# MCU042A_HOST_INTERFACE.net
KiCad netlist of a schematic drawn in Altium Designer
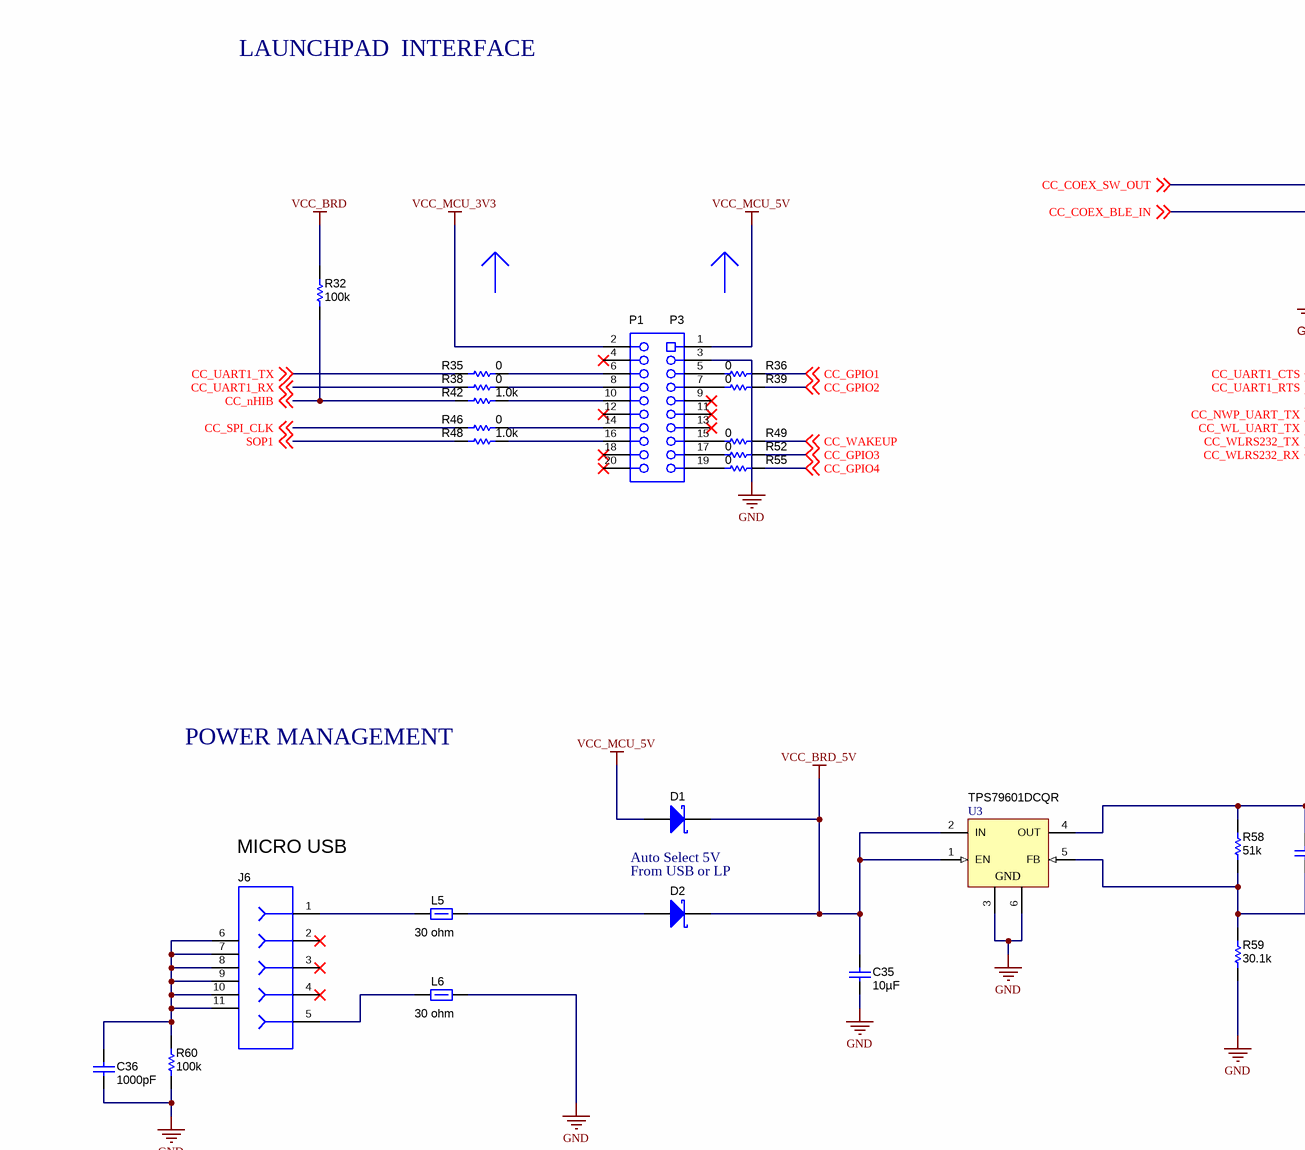
[diagram p0: MCU042A_HOST INTERFACE.SchDoc, top left]
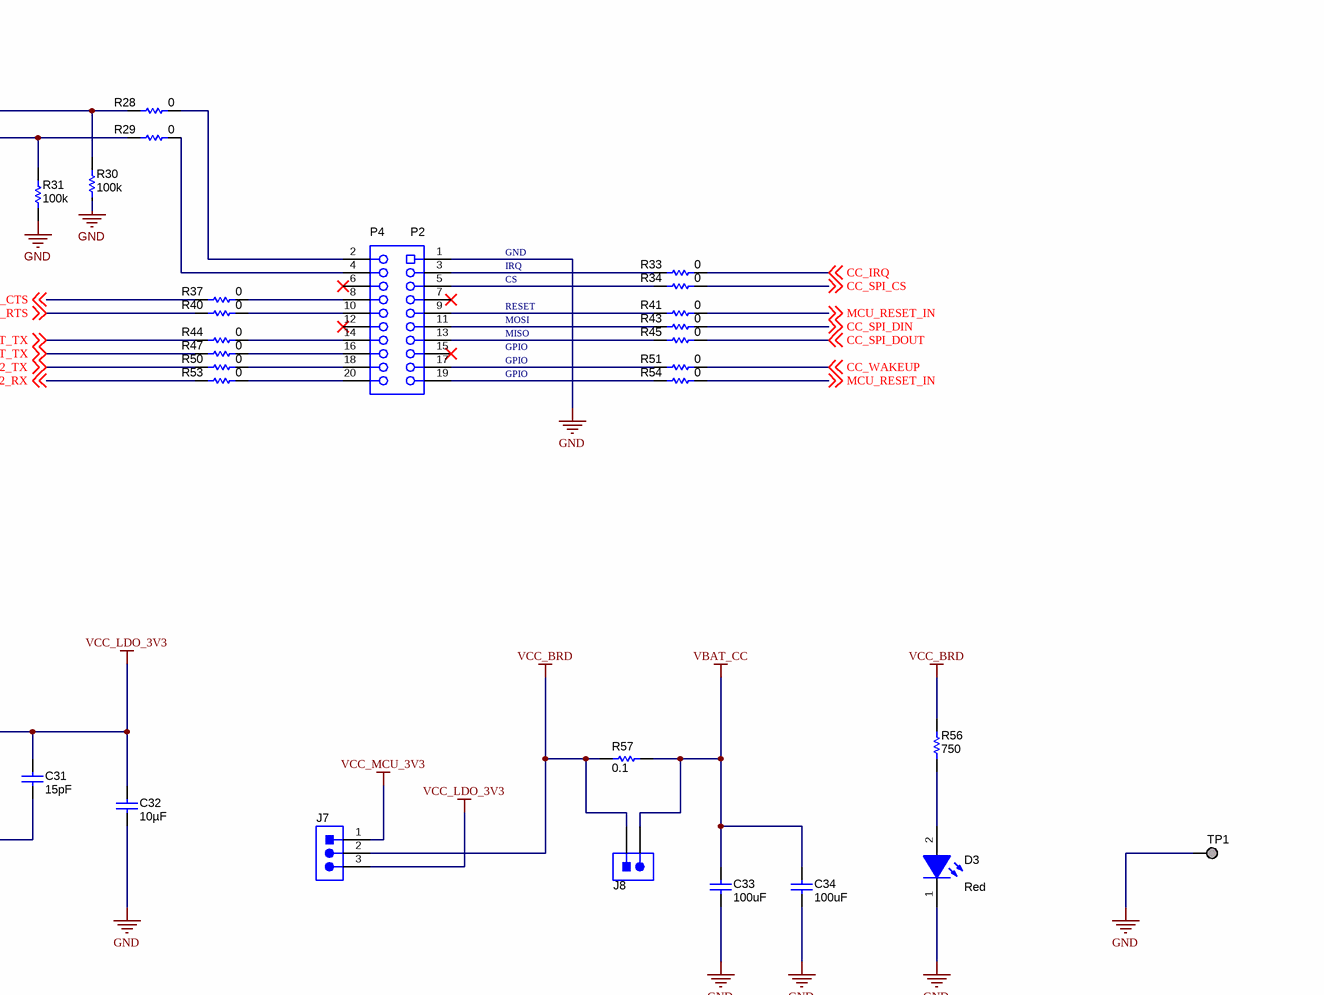
[diagram p1: MCU042A_HOST INTERFACE.SchDoc, top right]
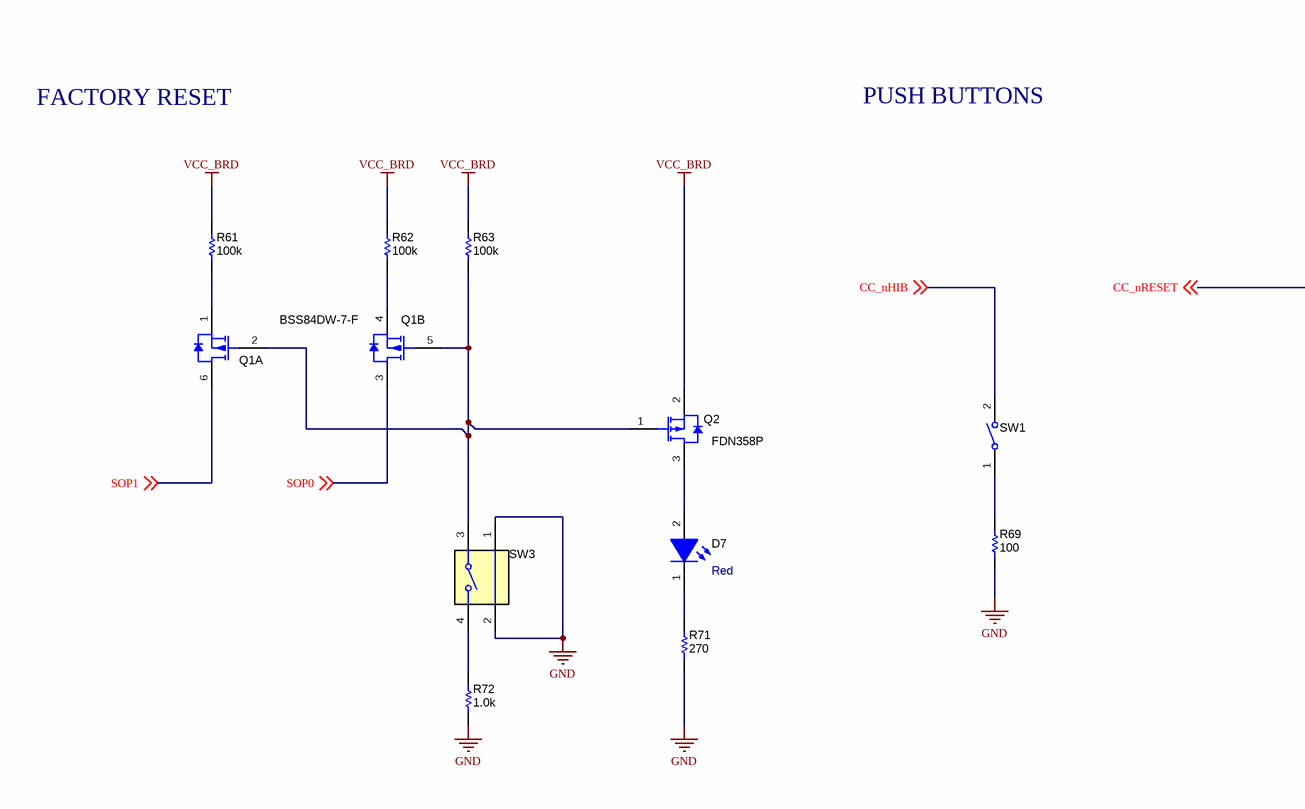
[diagram p2: MCU042A_HOST INTERFACE.SchDoc, bottom left]
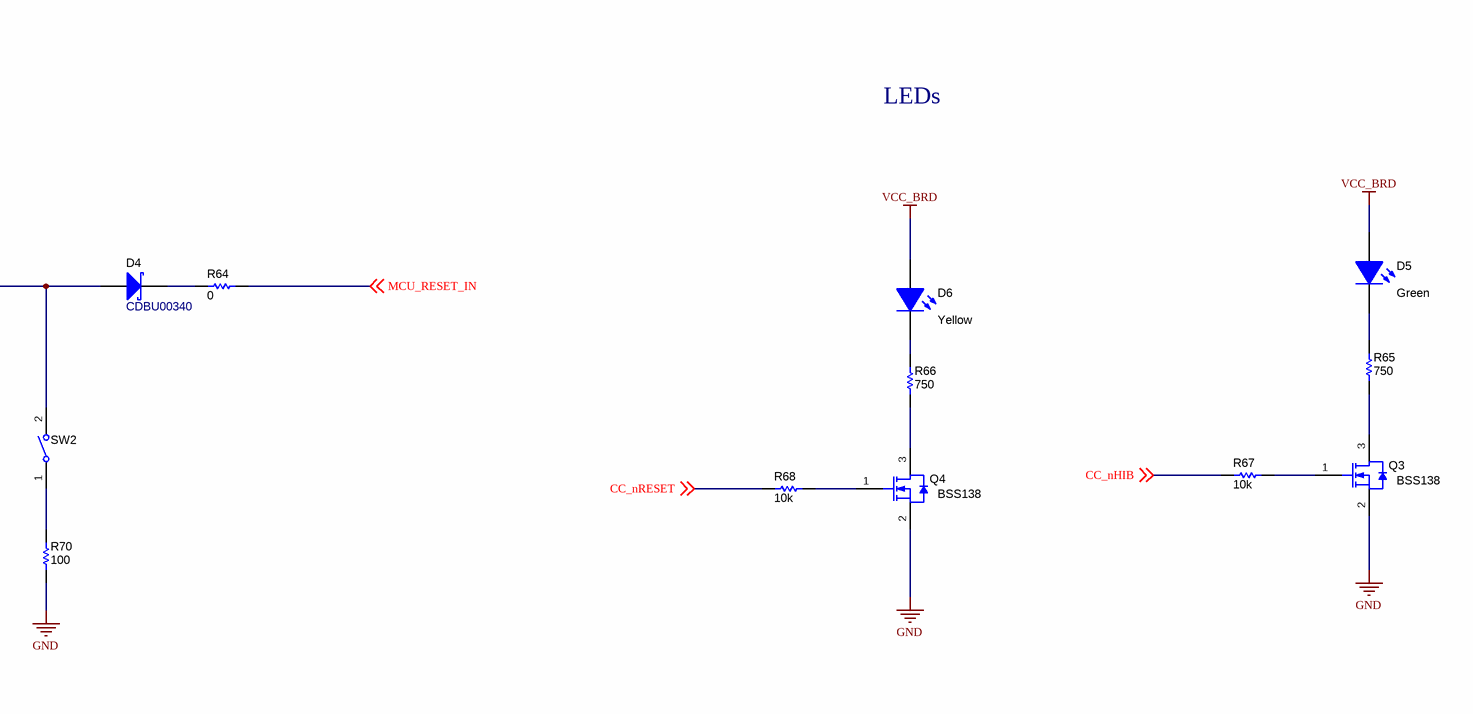
[diagram p3: MCU042A_HOST INTERFACE.SchDoc, bottom right]

(export (version "E")
  (design (tool "Eeschema 10.0.6"))
  (components
    (comp (ref "C31")
      (value "CMP-0006420-2")
      (footprint "0402")
      (description "CAP, CERM, 15 pF, 50 V, +/- 5%, C0G/NP0, 0402")
      (fields
        (field (name "PARTNUMBER") "CL05C150JB5NNNC")
        (field (name "VALUEDISPLAYED") "15pF")
        (field (name "MANUFACTURER") "SAMSUNG")
        (field (name "PUBLISHER") "Texas Instruments")
      )
      (libsource (lib "Altium Vault - TI") (part "CMP-0006420-2"))
    )
    (comp (ref "C32")
      (value "CL21A106KPFNNNE")
      (footprint "0805_HV")
      (description "CAP, CERM, 10 µF, 10 V,+/- 10%, X5R, 0805")
      (fields
        (field (name "VALUEDISPLAYED") "10µF")
        (field (name "MANUFACTURER") "Samsung Electro-Mechanics")
        (field (name "ALTERNATE PARTNUMBER") "GRM21BR61A106KE19L")
      )
      (libsource (lib "Altium Vault - TI") (part "Capacitor"))
    )
    (comp (ref "C33")
      (value "CMP-0008934-2")
      (footprint "1206_180")
      (description "CAP, CERM, 100 uF, 6.3 V, +/- 20%, X5R, 1206")
      (fields
        (field (name "PARTNUMBER") "GRM31CR60J107ME39L")
        (field (name "VALUEDISPLAYED") "100uF")
        (field (name "MANUFACTURER") "MuRata")
        (field (name "PUBLISHER") "Texas Instruments")
      )
      (libsource (lib "Altium Vault - TI") (part "CMP-0008934-2"))
    )
    (comp (ref "C34")
      (value "CMP-0008934-2")
      (footprint "1206_180")
      (description "CAP, CERM, 100 uF, 6.3 V, +/- 20%, X5R, 1206")
      (fields
        (field (name "PARTNUMBER") "GRM31CR60J107ME39L")
        (field (name "VALUEDISPLAYED") "100uF")
        (field (name "MANUFACTURER") "MuRata")
        (field (name "PUBLISHER") "Texas Instruments")
      )
      (libsource (lib "Altium Vault - TI") (part "CMP-0008934-2"))
    )
    (comp (ref "C35")
      (value "CL21A106KPFNNNE")
      (footprint "0805_HV")
      (description "CAP, CERM, 10 µF, 10 V,+/- 10%, X5R, 0805")
      (fields
        (field (name "VALUEDISPLAYED") "10µF")
        (field (name "MANUFACTURER") "Samsung Electro-Mechanics")
        (field (name "ALTERNATE PARTNUMBER") "GRM21BR61A106KE19L")
      )
      (libsource (lib "Altium Vault - TI") (part "Capacitor"))
    )
    (comp (ref "C36")
      (value "CL10B102KB8NNNC")
      (footprint "0603")
      (description "CAP, CERM, 1000 pF, 50 V,+/- 10%, X7R, 0603")
      (fields
        (field (name "VALUEDISPLAYED") "1000pF")
        (field (name "MANUFACTURER") "Samsung Electro-Mechanics")
        (field (name "ALTERNATE PARTNUMBER") "GRM188R61H102KA01D")
      )
      (libsource (lib "Altium Vault - TI") (part "Capacitor"))
    )
    (comp (ref "D1")
      (value "CMP-0028547-1")
      (footprint "SOD-123")
      (description "Diode, Schottky, 30 V, 1 A, SOD-123")
      (fields
        (field (name "PARTNUMBER") "MBR130T1G")
        (field (name "MANUFACTURER") "ON Semiconductor")
        (field (name "PUBLISHER") "Texas Instruments")
      )
      (libsource (lib "Altium Vault - TI") (part "CMP-0028547-1"))
    )
    (comp (ref "D2")
      (value "CMP-0028547-1")
      (footprint "SOD-123")
      (description "Diode, Schottky, 30 V, 1 A, SOD-123")
      (fields
        (field (name "PARTNUMBER") "MBR130T1G")
        (field (name "MANUFACTURER") "ON Semiconductor")
        (field (name "PUBLISHER") "Texas Instruments")
      )
      (libsource (lib "Altium Vault - TI") (part "CMP-0028547-1"))
    )
    (comp (ref "D3")
      (value "Red")
      (footprint "SML-31_Red")
      (description "LED, Red, SMD")
      (fields
        (field (name "MANUFACTURER") "Everlight")
        (field (name "PARTNUMBER") "19-217/R6C-AL1M2VY/3T")
        (field (name "PUBLISHER") "Texas Instruments")
      )
      (libsource (lib "Altium Vault - TI") (part "CMP-0002871-1"))
    )
    (comp (ref "D4")
      (value "CDBU00340")
      (footprint "SOD-523F")
      (description "Diode, Schottky, 45 V, 0.03 A, SOD-523F")
      (fields
        (field (name "MANUFACTURER") "Comchip Technology")
        (field (name "ALTERNATE PARTNUMBER") "CD0603-B00340")
      )
      (libsource (lib "Altium Vault - TI") (part "DIODE_SCHOTTKY"))
    )
    (comp (ref "D5")
      (value "Green")
      (footprint "WL-SMCW_GREEN")
      (description "LED, Green, SMD")
      (fields
        (field (name "MANUFACTURER") "Wurth Elektronik")
        (field (name "PARTNUMBER") "150060GS75000")
        (field (name "PUBLISHER") "Texas Instruments")
      )
      (libsource (lib "Altium Vault - TI") (part "CMP-0002905-1"))
    )
    (comp (ref "D6")
      (value "Yellow")
      (footprint "WL-SMCW_YELLOW")
      (description "LED, Yellow, SMD")
      (fields
        (field (name "MANUFACTURER") "Wurth Elektronik")
        (field (name "PARTNUMBER") "150060YS75000")
        (field (name "PUBLISHER") "Texas Instruments")
      )
      (libsource (lib "Altium Vault - TI") (part "CMP-0002892-2"))
    )
    (comp (ref "D7")
      (value "Red")
      (footprint "SML-31_Red")
      (description "LED, Red, SMD")
      (fields (field (name "MANUFACTURER") "everlight") (field (name "PARTNUMBER") "19-217/R6C-AL1M2VY/3T"))
      (libsource (lib "Altium Vault - TI") (part "LED_A2_K1"))
    )
    (comp (ref "J6")
      (value "105017-0001")
      (footprint "CONN_105017-0001")
      (description "Connector, Receptacle, Micro-USB Type B, R/A, Bottom Mount SMT")
      (fields
        (field (name "MANUFACTURER") "Molex")
        (field (name "ALTERNATE PARTNUMBER") "----")
        (field (name "SYMBOLCREATOR") "a0412235")
        (field (name "PUBLISHER") "Texas Instruments")
      )
      (libsource (lib "Altium Vault - TI") (part "CMP-0055293-1"))
    )
    (comp (ref "J7")
      (value "CMP-0075407-2")
      (footprint "TSW-103-07-G-S")
      (description "Header, 100mil, 3x1, Gold, TH")
      (fields (field (name "PARTNUMBER") "TSW-103-07-G-S") (field (name "MANUFACTURER") "Samtec"))
      (libsource (lib "Altium Vault - TI") (part "CMP-0075407-2"))
    )
    (comp (ref "J8")
      (value "CMP-0075500-1")
      (footprint "SAMTEC_HMTSW-102-07-G-S-240")
      (description "Header, 100mil, 2x1, Gold, TH")
      (fields
        (field (name "PARTNUMBER") "HMTSW-102-07-G-S-240")
        (field (name "MANUFACTURER") "Samtec")
        (field (name "PUBLISHER") "Texas Instruments")
      )
      (libsource (lib "Altium Vault - TI") (part "CMP-0075500-1"))
    )
    (comp (ref "L5")
      (value "30 ohm")
      (footprint "0805_HV")
      (description "Ferrite Bead, 30 ohm @ 100 MHz, 1.5 A, 0805")
      (fields
        (field (name "PARTNUMBER") "MMZ2012R300AT000")
        (field (name "MANUFACTURER") "TDK")
        (field (name "PUBLISHER") "Texas Instruments")
      )
      (libsource (lib "Altium Vault - TI") (part "CMP-0003418-1"))
    )
    (comp (ref "L6")
      (value "CMP-0003418-1")
      (footprint "0805_HV")
      (description "Ferrite Bead, 30 ohm @ 100 MHz, 1.5 A, 0805")
      (fields
        (field (name "PARTNUMBER") "MMZ2012R300AT000")
        (field (name "MANUFACTURER") "TDK")
        (field (name "VALUEDISPLAYED") "30 ohm")
        (field (name "PUBLISHER") "Texas Instruments")
      )
      (libsource (lib "") (part "CMP-0003418-1_1"))
    )
    (comp (ref "P1")
      (value "CMP-0075442-1")
      (footprint "CONN_SSW-110-23-F-D")
      (description "Connector, Receptacle, 100mil, 10x2, Gold plated, TH")
      (fields
        (field (name "PARTNUMBER") "SSW-110-23-F-D")
        (field (name "MANUFACTURER") "Samtec")
        (field (name "PUBLISHER") "Texas Instruments")
      )
      (libsource (lib "Altium Vault - TI") (part "CMP-0075442-1"))
    )
    (comp (ref "P2")
      (value "CMP-0075442-1")
      (footprint "CONN_SSW-110-23-F-D")
      (description "Connector, Receptacle, 100mil, 10x2, Gold plated, TH")
      (fields
        (field (name "PARTNUMBER") "SSW-110-23-F-D")
        (field (name "MANUFACTURER") "Samtec")
        (field (name "PUBLISHER") "Texas Instruments")
      )
      (libsource (lib "Altium Vault - TI") (part "CMP-0075442-1"))
    )
    (comp (ref "Q1")
      (value "CMP-0000014-2")
      (footprint "SOT-363")
      (description "MOSFET, 2-CH, P-CH, -50 V, -0.13 A, AEC-Q101, SOT-363")
      (fields
        (field (name "PARTNUMBER") "BSS84DW-7-F")
        (field (name "MANUFACTURER") "Diodes Inc.")
        (field (name "ALTERNATE PARTNUMBER") "----")
        (field (name "PUBLISHER") "Texas Instruments")
      )
      (libsource (lib "Altium Vault - TI") (part "CMP-0000014-2"))
    )
    (comp (ref "Q2")
      (value "CMP-0000059-2")
      (footprint "SSOT-3")
      (description "MOSFET, P-CH, -30 V, -1.5 A, SSOT-3")
      (fields
        (field (name "PARTNUMBER") "FDN358P")
        (field (name "MANUFACTURER") "Fairchild Semiconductor")
        (field (name "ALTERNATE PARTNUMBER") "----")
        (field (name "PUBLISHER") "Texas Instruments")
      )
      (libsource (lib "Altium Vault - TI") (part "CMP-0000059-2"))
    )
    (comp (ref "Q3")
      (value "CMP-0000755-1")
      (footprint "SOT-23")
      (description "MOSFET, N-CH, 50 V, 0.22 A, SOT-23")
      (fields
        (field (name "PARTNUMBER") "BSS138")
        (field (name "MANUFACTURER") "Fairchild Semiconductor")
        (field (name "ALTERNATE PARTNUMBER") "BSS138LT1G")
        (field (name "PUBLISHER") "Texas Instruments")
      )
      (libsource (lib "Altium Vault - TI") (part "CMP-0000755-1"))
    )
    (comp (ref "Q4")
      (value "CMP-0000755-1")
      (footprint "SOT-23")
      (description "MOSFET, N-CH, 50 V, 0.22 A, SOT-23")
      (fields
        (field (name "PARTNUMBER") "BSS138")
        (field (name "MANUFACTURER") "Fairchild Semiconductor")
        (field (name "ALTERNATE PARTNUMBER") "BSS138LT1G")
        (field (name "PUBLISHER") "Texas Instruments")
      )
      (libsource (lib "Altium Vault - TI") (part "CMP-0000755-1"))
    )
    (comp (ref "R28")
      (value "CMP-0026992-2")
      (footprint "0402")
      (description "RES, 0, 5%, 0.063 W, 0402")
      (fields
        (field (name "PARTNUMBER") "ERJ-2GE0R00X")
        (field (name "VALUEDISPLAYED") "0")
        (field (name "MANUFACTURER") "Panasonic")
        (field (name "PUBLISHER") "Texas Instruments")
      )
      (libsource (lib "Altium Vault - TI") (part "Resistor"))
    )
    (comp (ref "R29")
      (value "CMP-0026992-2")
      (footprint "0402")
      (description "RES, 0, 5%, 0.063 W, 0402")
      (fields
        (field (name "PARTNUMBER") "ERJ-2GE0R00X")
        (field (name "VALUEDISPLAYED") "0")
        (field (name "MANUFACTURER") "Panasonic")
        (field (name "PUBLISHER") "Texas Instruments")
      )
      (libsource (lib "Altium Vault - TI") (part "Resistor"))
    )
    (comp (ref "R30")
      (value "CMP-0026823-3")
      (footprint "0402")
      (description "RES, 100 k, 5%, 0.063 W, AEC-Q200 Grade 0, 0402")
      (fields
        (field (name "PARTNUMBER") "CRCW0402100KJNED")
        (field (name "VALUEDISPLAYED") "100k")
        (field (name "MANUFACTURER") "Vishay-Dale")
      )
      (libsource (lib "Altium Vault - TI") (part "Resistor"))
    )
    (comp (ref "R31")
      (value "CMP-0026823-3")
      (footprint "0402")
      (description "RES, 100 k, 5%, 0.063 W, AEC-Q200 Grade 0, 0402")
      (fields
        (field (name "PARTNUMBER") "CRCW0402100KJNED")
        (field (name "VALUEDISPLAYED") "100k")
        (field (name "MANUFACTURER") "Vishay-Dale")
      )
      (libsource (lib "Altium Vault - TI") (part "Resistor"))
    )
    (comp (ref "R32")
      (value "CMP-0021990-4")
      (footprint "0603")
      (description "RES, 100 k, 1%, 0.1 W, AEC-Q200 Grade 0, 0603")
      (fields
        (field (name "PARTNUMBER") "CRCW0603100KFKEA")
        (field (name "VALUEDISPLAYED") "100k")
        (field (name "MANUFACTURER") "Vishay-Dale")
      )
      (libsource (lib "Altium Vault - TI") (part "CMP-0021990-4"))
    )
    (comp (ref "R33")
      (value "CMP-0026992-2")
      (footprint "0402")
      (description "RES, 0, 5%, 0.063 W, 0402")
      (fields
        (field (name "PARTNUMBER") "ERJ-2GE0R00X")
        (field (name "VALUEDISPLAYED") "0")
        (field (name "MANUFACTURER") "Panasonic")
        (field (name "PUBLISHER") "Texas Instruments")
      )
      (libsource (lib "Altium Vault - TI") (part "Resistor"))
    )
    (comp (ref "R34")
      (value "CMP-0026992-2")
      (footprint "0402")
      (description "RES, 0, 5%, 0.063 W, 0402")
      (fields
        (field (name "PARTNUMBER") "ERJ-2GE0R00X")
        (field (name "VALUEDISPLAYED") "0")
        (field (name "MANUFACTURER") "Panasonic")
        (field (name "PUBLISHER") "Texas Instruments")
      )
      (libsource (lib "Altium Vault - TI") (part "Resistor"))
    )
    (comp (ref "R35")
      (value "CMP-0026992-2")
      (footprint "0402")
      (description "RES, 0, 5%, 0.063 W, 0402")
      (fields
        (field (name "PARTNUMBER") "ERJ-2GE0R00X")
        (field (name "VALUEDISPLAYED") "0")
        (field (name "MANUFACTURER") "Panasonic")
        (field (name "PUBLISHER") "Texas Instruments")
      )
      (libsource (lib "Altium Vault - TI") (part "Resistor"))
    )
    (comp (ref "R36")
      (value "CMP-0026992-2")
      (footprint "0402")
      (description "RES, 0, 5%, 0.063 W, 0402")
      (fields
        (field (name "PARTNUMBER") "ERJ-2GE0R00X")
        (field (name "VALUEDISPLAYED") "0")
        (field (name "MANUFACTURER") "Panasonic")
        (field (name "PUBLISHER") "Texas Instruments")
      )
      (libsource (lib "Altium Vault - TI") (part "Resistor"))
    )
    (comp (ref "R37")
      (value "CMP-0026992-2")
      (footprint "0402")
      (description "RES, 0, 5%, 0.063 W, 0402")
      (fields
        (field (name "PARTNUMBER") "ERJ-2GE0R00X")
        (field (name "VALUEDISPLAYED") "0")
        (field (name "MANUFACTURER") "Panasonic")
        (field (name "PUBLISHER") "Texas Instruments")
      )
      (libsource (lib "Altium Vault - TI") (part "Resistor"))
    )
    (comp (ref "R38")
      (value "CMP-0026992-2")
      (footprint "0402")
      (description "RES, 0, 5%, 0.063 W, 0402")
      (fields
        (field (name "PARTNUMBER") "ERJ-2GE0R00X")
        (field (name "VALUEDISPLAYED") "0")
        (field (name "MANUFACTURER") "Panasonic")
        (field (name "PUBLISHER") "Texas Instruments")
      )
      (libsource (lib "Altium Vault - TI") (part "Resistor"))
    )
    (comp (ref "R39")
      (value "CMP-0026992-2")
      (footprint "0402")
      (description "RES, 0, 5%, 0.063 W, 0402")
      (fields
        (field (name "PARTNUMBER") "ERJ-2GE0R00X")
        (field (name "VALUEDISPLAYED") "0")
        (field (name "MANUFACTURER") "Panasonic")
        (field (name "PUBLISHER") "Texas Instruments")
      )
      (libsource (lib "Altium Vault - TI") (part "Resistor"))
    )
    (comp (ref "R40")
      (value "CMP-0026992-2")
      (footprint "0402")
      (description "RES, 0, 5%, 0.063 W, 0402")
      (fields
        (field (name "PARTNUMBER") "ERJ-2GE0R00X")
        (field (name "VALUEDISPLAYED") "0")
        (field (name "MANUFACTURER") "Panasonic")
        (field (name "PUBLISHER") "Texas Instruments")
      )
      (libsource (lib "Altium Vault - TI") (part "Resistor"))
    )
    (comp (ref "R41")
      (value "CMP-0026992-2")
      (footprint "0402")
      (description "RES, 0, 5%, 0.063 W, 0402")
      (fields
        (field (name "PARTNUMBER") "ERJ-2GE0R00X")
        (field (name "VALUEDISPLAYED") "0")
        (field (name "MANUFACTURER") "Panasonic")
        (field (name "PUBLISHER") "Texas Instruments")
      )
      (libsource (lib "Altium Vault - TI") (part "Resistor"))
    )
    (comp (ref "R42")
      (value "CMP-0026852-3")
      (footprint "0402")
      (description "RES, 1.0 k, 5%, 0.063 W, AEC-Q200 Grade 0, 0402")
      (fields
        (field (name "PARTNUMBER") "CRCW04021K00JNED")
        (field (name "VALUEDISPLAYED") "1.0k")
        (field (name "MANUFACTURER") "Vishay-Dale")
      )
      (libsource (lib "Altium Vault - TI") (part "Resistor"))
    )
    (comp (ref "R43")
      (value "CMP-0026992-2")
      (footprint "0402")
      (description "RES, 0, 5%, 0.063 W, 0402")
      (fields
        (field (name "PARTNUMBER") "ERJ-2GE0R00X")
        (field (name "VALUEDISPLAYED") "0")
        (field (name "MANUFACTURER") "Panasonic")
        (field (name "PUBLISHER") "Texas Instruments")
      )
      (libsource (lib "Altium Vault - TI") (part "Resistor"))
    )
    (comp (ref "R44")
      (value "CMP-0026992-2")
      (footprint "0402")
      (description "RES, 0, 5%, 0.063 W, 0402")
      (fields
        (field (name "PARTNUMBER") "ERJ-2GE0R00X")
        (field (name "VALUEDISPLAYED") "0")
        (field (name "MANUFACTURER") "Panasonic")
        (field (name "PUBLISHER") "Texas Instruments")
      )
      (libsource (lib "Altium Vault - TI") (part "Resistor"))
    )
    (comp (ref "R45")
      (value "CMP-0026992-2")
      (footprint "0402")
      (description "RES, 0, 5%, 0.063 W, 0402")
      (fields
        (field (name "PARTNUMBER") "ERJ-2GE0R00X")
        (field (name "VALUEDISPLAYED") "0")
        (field (name "MANUFACTURER") "Panasonic")
        (field (name "PUBLISHER") "Texas Instruments")
      )
      (libsource (lib "Altium Vault - TI") (part "Resistor"))
    )
    (comp (ref "R46")
      (value "CMP-0026992-2")
      (footprint "0402")
      (description "RES, 0, 5%, 0.063 W, 0402")
      (fields
        (field (name "PARTNUMBER") "ERJ-2GE0R00X")
        (field (name "VALUEDISPLAYED") "0")
        (field (name "MANUFACTURER") "Panasonic")
        (field (name "PUBLISHER") "Texas Instruments")
      )
      (libsource (lib "Altium Vault - TI") (part "Resistor"))
    )
    (comp (ref "R47")
      (value "CMP-0026992-2")
      (footprint "0402")
      (description "RES, 0, 5%, 0.063 W, 0402")
      (fields
        (field (name "PARTNUMBER") "ERJ-2GE0R00X")
        (field (name "VALUEDISPLAYED") "0")
        (field (name "MANUFACTURER") "Panasonic")
        (field (name "PUBLISHER") "Texas Instruments")
      )
      (libsource (lib "Altium Vault - TI") (part "Resistor"))
    )
    (comp (ref "R48")
      (value "CMP-0026852-3")
      (footprint "0402")
      (description "RES, 1.0 k, 5%, 0.063 W, AEC-Q200 Grade 0, 0402")
      (fields
        (field (name "PARTNUMBER") "CRCW04021K00JNED")
        (field (name "VALUEDISPLAYED") "1.0k")
        (field (name "MANUFACTURER") "Vishay-Dale")
      )
      (libsource (lib "Altium Vault - TI") (part "Resistor"))
    )
    (comp (ref "R49")
      (value "CMP-0026992-2")
      (footprint "0402")
      (description "RES, 0, 5%, 0.063 W, 0402")
      (fields
        (field (name "PARTNUMBER") "ERJ-2GE0R00X")
        (field (name "VALUEDISPLAYED") "0")
        (field (name "MANUFACTURER") "Panasonic")
        (field (name "PUBLISHER") "Texas Instruments")
      )
      (libsource (lib "Altium Vault - TI") (part "Resistor"))
    )
    (comp (ref "R50")
      (value "CMP-0026992-2")
      (footprint "0402")
      (description "RES, 0, 5%, 0.063 W, 0402")
      (fields
        (field (name "PARTNUMBER") "ERJ-2GE0R00X")
        (field (name "VALUEDISPLAYED") "0")
        (field (name "MANUFACTURER") "Panasonic")
        (field (name "PUBLISHER") "Texas Instruments")
      )
      (libsource (lib "Altium Vault - TI") (part "Resistor"))
    )
    (comp (ref "R51")
      (value "CMP-0026992-2")
      (footprint "0402")
      (description "RES, 0, 5%, 0.063 W, 0402")
      (fields
        (field (name "PARTNUMBER") "ERJ-2GE0R00X")
        (field (name "VALUEDISPLAYED") "0")
        (field (name "MANUFACTURER") "Panasonic")
        (field (name "PUBLISHER") "Texas Instruments")
      )
      (libsource (lib "Altium Vault - TI") (part "Resistor"))
    )
    (comp (ref "R52")
      (value "CMP-0026992-2")
      (footprint "0402")
      (description "RES, 0, 5%, 0.063 W, 0402")
      (fields
        (field (name "PARTNUMBER") "ERJ-2GE0R00X")
        (field (name "VALUEDISPLAYED") "0")
        (field (name "MANUFACTURER") "Panasonic")
        (field (name "PUBLISHER") "Texas Instruments")
      )
      (libsource (lib "Altium Vault - TI") (part "Resistor"))
    )
    (comp (ref "R53")
      (value "CMP-0026992-2")
      (footprint "0402")
      (description "RES, 0, 5%, 0.063 W, 0402")
      (fields
        (field (name "PARTNUMBER") "ERJ-2GE0R00X")
        (field (name "VALUEDISPLAYED") "0")
        (field (name "MANUFACTURER") "Panasonic")
        (field (name "PUBLISHER") "Texas Instruments")
      )
      (libsource (lib "Altium Vault - TI") (part "Resistor"))
    )
    (comp (ref "R54")
      (value "CMP-0026992-2")
      (footprint "0402")
      (description "RES, 0, 5%, 0.063 W, 0402")
      (fields
        (field (name "PARTNUMBER") "ERJ-2GE0R00X")
        (field (name "VALUEDISPLAYED") "0")
        (field (name "MANUFACTURER") "Panasonic")
        (field (name "PUBLISHER") "Texas Instruments")
      )
      (libsource (lib "Altium Vault - TI") (part "Resistor"))
    )
    (comp (ref "R55")
      (value "CMP-0026992-2")
      (footprint "0402")
      (description "RES, 0, 5%, 0.063 W, 0402")
      (fields
        (field (name "PARTNUMBER") "ERJ-2GE0R00X")
        (field (name "VALUEDISPLAYED") "0")
        (field (name "MANUFACTURER") "Panasonic")
        (field (name "PUBLISHER") "Texas Instruments")
      )
      (libsource (lib "Altium Vault - TI") (part "Resistor"))
    )
    (comp (ref "R56")
      (value "CMP-0025852-4")
      (footprint "0603")
      (description "RES, 750, 5%, 0.1 W, AEC-Q200 Grade 0, 0603")
      (fields
        (field (name "PARTNUMBER") "CRCW0603750RJNEA")
        (field (name "VALUEDISPLAYED") "750")
        (field (name "MANUFACTURER") "Vishay-Dale")
      )
      (libsource (lib "Altium Vault - TI") (part "Resistor"))
    )
    (comp (ref "R57")
      (value "CMP-0021515-2")
      (footprint "0805_HV")
      (description "RES, 0.1, 1%, 0.25 W, 0805")
      (fields
        (field (name "PARTNUMBER") "CRM0805-FX-R100ELF")
        (field (name "VALUEDISPLAYED") "0.1")
        (field (name "MANUFACTURER") "Bourns")
        (field (name "PUBLISHER") "Texas Instruments")
      )
      (libsource (lib "Altium Vault - TI") (part "CMP-0021515-2"))
    )
    (comp (ref "R58")
      (value "CMP-0026945-3")
      (footprint "0402")
      (description "RES, 51 k, 5%, 0.063 W, AEC-Q200 Grade 0, 0402")
      (fields
        (field (name "PARTNUMBER") "CRCW040251K0JNED")
        (field (name "VALUEDISPLAYED") "51k")
        (field (name "MANUFACTURER") "Vishay-Dale")
      )
      (libsource (lib "Altium Vault - TI") (part "CMP-0026945-3"))
    )
    (comp (ref "R59")
      (value "CMP-0026284-2")
      (footprint "0402")
      (description "RES, 30.1 k, 1%, 0.063 W, AEC-Q200 Grade 0, 0402")
      (fields
        (field (name "PARTNUMBER") "CRCW040230K1FKED")
        (field (name "VALUEDISPLAYED") "30.1k")
        (field (name "MANUFACTURER") "Vishay-Dale")
      )
      (libsource (lib "Altium Vault - TI") (part "CMP-0026284-2"))
    )
    (comp (ref "R60")
      (value "CMP-0026823-3")
      (footprint "0402")
      (description "RES, 100 k, 5%, 0.063 W, AEC-Q200 Grade 0, 0402")
      (fields
        (field (name "PARTNUMBER") "CRCW0402100KJNED")
        (field (name "VALUEDISPLAYED") "100k")
        (field (name "MANUFACTURER") "Vishay-Dale")
      )
      (libsource (lib "Altium Vault - TI") (part "Resistor"))
    )
    (comp (ref "R61")
      (value "CMP-0026659-1")
      (footprint "0402")
      (description "RES, 100 k, 1%, 0.1 W, 0402")
      (fields
        (field (name "PARTNUMBER") "ERJ-2RKF1003X")
        (field (name "VALUEDISPLAYED") "100k")
        (field (name "MANUFACTURER") "Panasonic")
        (field (name "PUBLISHER") "Texas Instruments")
      )
      (libsource (lib "Altium Vault - TI") (part "Resistor"))
    )
    (comp (ref "R62")
      (value "CMP-0026659-1")
      (footprint "0402")
      (description "RES, 100 k, 1%, 0.1 W, 0402")
      (fields
        (field (name "PARTNUMBER") "ERJ-2RKF1003X")
        (field (name "VALUEDISPLAYED") "100k")
        (field (name "MANUFACTURER") "Panasonic")
        (field (name "PUBLISHER") "Texas Instruments")
      )
      (libsource (lib "Altium Vault - TI") (part "Resistor"))
    )
    (comp (ref "R63")
      (value "CMP-0026659-1")
      (footprint "0402")
      (description "RES, 100 k, 1%, 0.1 W, 0402")
      (fields
        (field (name "PARTNUMBER") "ERJ-2RKF1003X")
        (field (name "VALUEDISPLAYED") "100k")
        (field (name "MANUFACTURER") "Panasonic")
        (field (name "PUBLISHER") "Texas Instruments")
      )
      (libsource (lib "Altium Vault - TI") (part "Resistor"))
    )
    (comp (ref "R64")
      (value "CMP-0025874-3")
      (footprint "0603")
      (description "RES, 0, 5%, 0.1 W, 0603")
      (fields
        (field (name "PARTNUMBER") "ERJ-3GEY0R00V")
        (field (name "VALUEDISPLAYED") "0")
        (field (name "MANUFACTURER") "Panasonic")
        (field (name "PUBLISHER") "Texas Instruments")
      )
      (libsource (lib "Altium Vault - TI") (part "CMP-0025874-3"))
    )
    (comp (ref "R65")
      (value "CMP-0025852-4")
      (footprint "0603")
      (description "RES, 750, 5%, 0.1 W, AEC-Q200 Grade 0, 0603")
      (fields
        (field (name "PARTNUMBER") "CRCW0603750RJNEA")
        (field (name "VALUEDISPLAYED") "750")
        (field (name "MANUFACTURER") "Vishay-Dale")
      )
      (libsource (lib "Altium Vault - TI") (part "Resistor"))
    )
    (comp (ref "R66")
      (value "CMP-0025852-4")
      (footprint "0603")
      (description "RES, 750, 5%, 0.1 W, AEC-Q200 Grade 0, 0603")
      (fields
        (field (name "PARTNUMBER") "CRCW0603750RJNEA")
        (field (name "VALUEDISPLAYED") "750")
        (field (name "MANUFACTURER") "Vishay-Dale")
      )
      (libsource (lib "Altium Vault - TI") (part "Resistor"))
    )
    (comp (ref "R67")
      (value "CMP-0026825-5")
      (footprint "0402")
      (description "RES, 10 k, 5%, 0.063 W, AEC-Q200 Grade 0, 0402")
      (fields
        (field (name "PARTNUMBER") "CRCW040210K0JNED")
        (field (name "VALUEDISPLAYED") "10k")
        (field (name "MANUFACTURER") "Vishay-Dale")
      )
      (libsource (lib "Altium Vault - TI") (part "Resistor"))
    )
    (comp (ref "R68")
      (value "CMP-0026825-5")
      (footprint "0402")
      (description "RES, 10 k, 5%, 0.063 W, AEC-Q200 Grade 0, 0402")
      (fields
        (field (name "PARTNUMBER") "CRCW040210K0JNED")
        (field (name "VALUEDISPLAYED") "10k")
        (field (name "MANUFACTURER") "Vishay-Dale")
      )
      (libsource (lib "Altium Vault - TI") (part "Resistor"))
    )
    (comp (ref "R69")
      (value "CMP-0026656-1")
      (footprint "0402")
      (description "RES, 100, 1%, 0.1 W, 0402")
      (fields
        (field (name "PARTNUMBER") "ERJ-2RKF1000X")
        (field (name "VALUEDISPLAYED") "100")
        (field (name "MANUFACTURER") "Panasonic")
        (field (name "PUBLISHER") "Texas Instruments")
      )
      (libsource (lib "Altium Vault - TI") (part "CMP-0026656-1"))
    )
    (comp (ref "R70")
      (value "CMP-0026656-1")
      (footprint "0402")
      (description "RES, 100, 1%, 0.1 W, 0402")
      (fields
        (field (name "PARTNUMBER") "ERJ-2RKF1000X")
        (field (name "VALUEDISPLAYED") "100")
        (field (name "MANUFACTURER") "Panasonic")
        (field (name "PUBLISHER") "Texas Instruments")
      )
      (libsource (lib "Altium Vault - TI") (part "CMP-0026656-1"))
    )
    (comp (ref "R71")
      (value "CMP-0025765-4")
      (footprint "0603")
      (description "RES, 270, 5%, 0.1 W, AEC-Q200 Grade 0, 0603")
      (fields
        (field (name "PARTNUMBER") "CRCW0603270RJNEA")
        (field (name "VALUEDISPLAYED") "270")
        (field (name "MANUFACTURER") "Vishay-Dale")
      )
      (libsource (lib "Altium Vault - TI") (part "CMP-0025765-4"))
    )
    (comp (ref "R72")
      (value "CMP-0026852-3")
      (footprint "0402")
      (description "RES, 1.0 k, 5%, 0.063 W, AEC-Q200 Grade 0, 0402")
      (fields
        (field (name "PARTNUMBER") "CRCW04021K00JNED")
        (field (name "VALUEDISPLAYED") "1.0k")
        (field (name "MANUFACTURER") "Vishay-Dale")
      )
      (libsource (lib "Altium Vault - TI") (part "CMP-0026852-3"))
    )
    (comp (ref "SW1")
      (value "CMP-0002249-1")
      (footprint "SW_MJTP1117")
      (description "Switch, SPST-NO, Off-Mom, 1 Pos, 0.05A, 12VDC, TH")
      (fields
        (field (name "PARTNUMBER") "MJTP1117")
        (field (name "MANUFACTURER") "APEM")
        (field (name "PUBLISHER") "Texas Instruments")
      )
      (libsource (lib "Altium Vault - TI") (part "CMP-0002249-1"))
    )
    (comp (ref "SW2")
      (value "CMP-0002249-1")
      (footprint "SW_MJTP1117")
      (description "Switch, SPST-NO, Off-Mom, 1 Pos, 0.05A, 12VDC, TH")
      (fields
        (field (name "PARTNUMBER") "MJTP1117")
        (field (name "MANUFACTURER") "APEM")
        (field (name "PUBLISHER") "Texas Instruments")
      )
      (libsource (lib "Altium Vault - TI") (part "CMP-0002249-1"))
    )
    (comp (ref "SW3")
      (value "1188E-1K2-V-TR")
      (footprint "SW_1188E")
      (description "Switch, SPST, 0.05 A, 12 VDC, SMD")
      (fields (field (name "MANUFACTURER") "Diptronics") (field (name "PUBLISHER") "Texas Instruments"))
      (libsource (lib "Altium Vault - TI") (part "SW_1188E"))
    )
    (comp (ref "TP1")
      (value "CMP-0003719-1")
      (footprint "TP_H045P075")
      (description "Testpoint")
      (fields
        (field (name "PARTNUMBER") "TP_H0.45P0.75")
        (field (name "MANUFACTURER") "Texas Instruments")
        (field (name "PUBLISHER") "Texas Instruments")
      )
      (libsource (lib "Altium Vault - TI") (part "CMP-0003719-1"))
    )
    (comp (ref "U3")
      (value "TPS79601DCQR")
      (footprint "DCQ0006A_N")
      (fields
        (field (name "PARTNUMBER") "TPS79601DCQR")
        (field (name "MANUFACTURER") "Texas Instruments")
        (field (name "ALTERNATE PARTNUMBER") "----")
      )
      (libsource (lib "Altium Vault - TI") (part "CMP-0036699-1"))
    )
  )
  (nets
    (net (code "1") (name "CC_COEX_BLE_IN") (class "Default")
      (node (ref "R29") (pin "1") (pinfunction "1_1") (pintype "passive"))
      (node (ref "R31") (pin "1") (pinfunction "1_1") (pintype "passive"))
    )
    (net (code "2") (name "CC_COEX_SW_OUT") (class "Default")
      (node (ref "R28") (pin "1") (pinfunction "1_1") (pintype "passive"))
      (node (ref "R30") (pin "1") (pinfunction "1_1") (pintype "passive"))
    )
    (net (code "3") (name "CC_GPIO1") (class "Default")
      (node (ref "R36") (pin "2") (pinfunction "2_2") (pintype "passive"))
    )
    (net (code "4") (name "CC_GPIO2") (class "Default")
      (node (ref "R39") (pin "2") (pinfunction "2_2") (pintype "passive"))
    )
    (net (code "5") (name "CC_GPIO3") (class "Default")
      (node (ref "R52") (pin "2") (pinfunction "2_2") (pintype "passive"))
    )
    (net (code "6") (name "CC_GPIO4") (class "Default")
      (node (ref "R55") (pin "2") (pinfunction "2_2") (pintype "passive"))
    )
    (net (code "7") (name "CC_IRQ") (class "Default")
      (node (ref "R33") (pin "2") (pinfunction "2_2") (pintype "passive"))
    )
    (net (code "8") (name "CC_NWP_UART_TX") (class "Default")
      (node (ref "R44") (pin "1") (pinfunction "1_1") (pintype "passive"))
    )
    (net (code "9") (name "CC_SPI_CLK") (class "Default")
      (node (ref "R46") (pin "1") (pinfunction "1_1") (pintype "passive"))
    )
    (net (code "10") (name "CC_SPI_CS") (class "Default")
      (node (ref "R34") (pin "2") (pinfunction "2_2") (pintype "passive"))
    )
    (net (code "11") (name "CC_SPI_DIN") (class "Default")
      (node (ref "R43") (pin "2") (pinfunction "2_2") (pintype "passive"))
    )
    (net (code "12") (name "CC_SPI_DOUT") (class "Default")
      (node (ref "R45") (pin "2") (pinfunction "2_2") (pintype "passive"))
    )
    (net (code "13") (name "CC_UART1_CTS") (class "Default")
      (node (ref "R37") (pin "1") (pinfunction "1_1") (pintype "passive"))
    )
    (net (code "14") (name "CC_UART1_RTS") (class "Default")
      (node (ref "R40") (pin "1") (pinfunction "1_1") (pintype "passive"))
    )
    (net (code "15") (name "CC_UART1_RX") (class "Default")
      (node (ref "R38") (pin "1") (pinfunction "1_1") (pintype "passive"))
    )
    (net (code "16") (name "CC_UART1_TX") (class "Default")
      (node (ref "R35") (pin "1") (pinfunction "1_1") (pintype "passive"))
    )
    (net (code "17") (name "CC_WAKEUP") (class "Default")
      (node (ref "R49") (pin "2") (pinfunction "2_2") (pintype "passive"))
      (node (ref "R51") (pin "2") (pinfunction "2_2") (pintype "passive"))
    )
    (net (code "18") (name "CC_WLRS232_RX") (class "Default")
      (node (ref "R53") (pin "1") (pinfunction "1_1") (pintype "passive"))
    )
    (net (code "19") (name "CC_WLRS232_TX") (class "Default")
      (node (ref "R50") (pin "1") (pinfunction "1_1") (pintype "passive"))
    )
    (net (code "20") (name "CC_WL_UART_TX") (class "Default")
      (node (ref "R47") (pin "1") (pinfunction "1_1") (pintype "passive"))
    )
    (net (code "21") (name "CC_nHIB") (class "Default")
      (node (ref "R32") (pin "1") (pinfunction "1_1") (pintype "passive"))
      (node (ref "R42") (pin "1") (pinfunction "1_1") (pintype "passive"))
      (node (ref "R67") (pin "1") (pinfunction "1_1") (pintype "passive"))
      (node (ref "SW1") (pin "2") (pinfunction "2_2") (pintype "passive"))
    )
    (net (code "22") (name "CC_nRESET") (class "Default")
      (node (ref "D4") (pin "2") (pinfunction "A_2") (pintype "passive"))
      (node (ref "R68") (pin "1") (pinfunction "1_1") (pintype "passive"))
      (node (ref "SW2") (pin "2") (pinfunction "2_2") (pintype "passive"))
    )
    (net (code "23") (name "GND") (class "Default")
      (node (ref "C32") (pin "2") (pinfunction "2_2") (pintype "passive"))
      (node (ref "C33") (pin "2") (pinfunction "2_2") (pintype "passive"))
      (node (ref "C34") (pin "2") (pinfunction "2_2") (pintype "passive"))
      (node (ref "C35") (pin "2") (pinfunction "2_2") (pintype "passive"))
      (node (ref "C36") (pin "2") (pinfunction "2_2") (pintype "passive"))
      (node (ref "D3") (pin "1") (pinfunction "K_1") (pintype "passive"))
      (node (ref "L6") (pin "1") (pinfunction "1_1") (pintype "passive"))
      (node (ref "P1") (pin "1") (pinfunction "1_1") (pintype "passive"))
      (node (ref "P2") (pin "3") (pinfunction "3_3") (pintype "passive"))
      (node (ref "Q3") (pin "2") (pinfunction "S_2") (pintype "passive"))
      (node (ref "Q4") (pin "2") (pinfunction "S_2") (pintype "passive"))
      (node (ref "R30") (pin "2") (pinfunction "2_2") (pintype "passive"))
      (node (ref "R31") (pin "2") (pinfunction "2_2") (pintype "passive"))
      (node (ref "R59") (pin "1") (pinfunction "1_1") (pintype "passive"))
      (node (ref "R60") (pin "2") (pinfunction "2_2") (pintype "passive"))
      (node (ref "R69") (pin "1") (pinfunction "1_1") (pintype "passive"))
      (node (ref "R70") (pin "1") (pinfunction "1_1") (pintype "passive"))
      (node (ref "R71") (pin "1") (pinfunction "1_1") (pintype "passive"))
      (node (ref "R72") (pin "1") (pinfunction "1_1") (pintype "passive"))
      (node (ref "SW3") (pin "1") (pinfunction "1_1") (pintype "passive"))
      (node (ref "SW3") (pin "2") (pinfunction "2_2") (pintype "passive"))
      (node (ref "TP1") (pin "1") (pintype "passive"))
      (node (ref "U3") (pin "3") (pinfunction "GND_3") (pintype "power_in"))
      (node (ref "U3") (pin "6") (pinfunction "GND_6") (pintype "power_in"))
    )
    (net (code "24") (name "MCU_RESET_IN") (class "Default")
      (node (ref "R41") (pin "2") (pinfunction "2_2") (pintype "passive"))
      (node (ref "R54") (pin "2") (pinfunction "2_2") (pintype "passive"))
      (node (ref "R64") (pin "2") (pinfunction "2_2") (pintype "passive"))
    )
    (net (code "25") (name "Net-(C36-Pad1)") (class "Default")
      (node (ref "C36") (pin "1") (pinfunction "1_1") (pintype "passive"))
      (node (ref "J6") (pin "10") (pintype "passive"))
      (node (ref "J6") (pin "11") (pintype "passive"))
      (node (ref "J6") (pin "6") (pintype "passive"))
      (node (ref "J6") (pin "7") (pintype "passive"))
      (node (ref "J6") (pin "8") (pintype "passive"))
      (node (ref "J6") (pin "9") (pintype "passive"))
      (node (ref "R60") (pin "1") (pinfunction "1_1") (pintype "passive"))
    )
    (net (code "26") (name "Net-(D2-A)") (class "Default")
      (node (ref "D2") (pin "2") (pinfunction "A_2") (pintype "passive"))
      (node (ref "L5") (pin "2") (pinfunction "2_2") (pintype "passive"))
    )
    (net (code "27") (name "Net-(D3-A)") (class "Default")
      (node (ref "D3") (pin "2") (pinfunction "A_2") (pintype "passive"))
      (node (ref "R56") (pin "2") (pinfunction "2_2") (pintype "passive"))
    )
    (net (code "28") (name "Net-(D4-K)") (class "Default")
      (node (ref "D4") (pin "1") (pinfunction "K_1") (pintype "passive"))
      (node (ref "R64") (pin "1") (pinfunction "1_1") (pintype "passive"))
    )
    (net (code "29") (name "Net-(D5-K)") (class "Default")
      (node (ref "D5") (pin "1") (pinfunction "K_1") (pintype "passive"))
      (node (ref "R65") (pin "1") (pinfunction "1_1") (pintype "passive"))
    )
    (net (code "30") (name "Net-(D6-K)") (class "Default")
      (node (ref "D6") (pin "1") (pinfunction "K_1") (pintype "passive"))
      (node (ref "R66") (pin "1") (pinfunction "1_1") (pintype "passive"))
    )
    (net (code "31") (name "Net-(D7-A)") (class "Default")
      (node (ref "D7") (pin "2") (pinfunction "A_2") (pintype "passive"))
      (node (ref "Q2") (pin "3") (pinfunction "D_3") (pintype "passive"))
    )
    (net (code "32") (name "Net-(D7-K)") (class "Default")
      (node (ref "D7") (pin "1") (pinfunction "K_1") (pintype "passive"))
      (node (ref "R71") (pin "2") (pinfunction "2_2") (pintype "passive"))
    )
    (net (code "33") (name "Net-(J6-Pad1)") (class "Default")
      (node (ref "J6") (pin "1") (pintype "passive"))
      (node (ref "L5") (pin "1") (pinfunction "1_1") (pintype "passive"))
    )
    (net (code "34") (name "Net-(J6-Pad5)") (class "Default")
      (node (ref "J6") (pin "5") (pintype "passive"))
      (node (ref "L6") (pin "2") (pinfunction "2_2") (pintype "passive"))
    )
    (net (code "35") (name "Net-(P1-Pad2)") (class "Default")
      (node (ref "P1") (pin "2") (pinfunction "2_2") (pintype "passive"))
      (node (ref "R28") (pin "2") (pinfunction "2_2") (pintype "passive"))
    )
    (net (code "36") (name "Net-(P1-Pad3)") (class "Default")
      (node (ref "P1") (pin "3") (pinfunction "3_3") (pintype "passive"))
      (node (ref "R33") (pin "1") (pinfunction "1_1") (pintype "passive"))
    )
    (net (code "37") (name "Net-(P1-Pad4)") (class "Default")
      (node (ref "P1") (pin "4") (pinfunction "4_4") (pintype "passive"))
      (node (ref "R29") (pin "2") (pinfunction "2_2") (pintype "passive"))
    )
    (net (code "38") (name "Net-(P1-Pad5)") (class "Default")
      (node (ref "P1") (pin "5") (pinfunction "5_5") (pintype "passive"))
      (node (ref "R34") (pin "1") (pinfunction "1_1") (pintype "passive"))
    )
    (net (code "39") (name "Net-(P1-Pad8)") (class "Default")
      (node (ref "P1") (pin "8") (pinfunction "8_8") (pintype "passive"))
      (node (ref "R37") (pin "2") (pinfunction "2_2") (pintype "passive"))
    )
    (net (code "40") (name "Net-(P1-Pad9)") (class "Default")
      (node (ref "P1") (pin "9") (pinfunction "9_9") (pintype "passive"))
      (node (ref "R41") (pin "1") (pinfunction "1_1") (pintype "passive"))
    )
    (net (code "41") (name "Net-(P1-Pad10)") (class "Default")
      (node (ref "P1") (pin "10") (pinfunction "10_10") (pintype "passive"))
      (node (ref "R40") (pin "2") (pinfunction "2_2") (pintype "passive"))
    )
    (net (code "42") (name "Net-(P1-Pad11)") (class "Default")
      (node (ref "P1") (pin "11") (pinfunction "11_11") (pintype "passive"))
      (node (ref "R43") (pin "1") (pinfunction "1_1") (pintype "passive"))
    )
    (net (code "43") (name "Net-(P1-Pad13)") (class "Default")
      (node (ref "P1") (pin "13") (pinfunction "13_13") (pintype "passive"))
      (node (ref "R45") (pin "1") (pinfunction "1_1") (pintype "passive"))
    )
    (net (code "44") (name "Net-(P1-Pad14)") (class "Default")
      (node (ref "P1") (pin "14") (pinfunction "14_14") (pintype "passive"))
      (node (ref "R44") (pin "2") (pinfunction "2_2") (pintype "passive"))
    )
    (net (code "45") (name "Net-(P1-Pad16)") (class "Default")
      (node (ref "P1") (pin "16") (pinfunction "16_16") (pintype "passive"))
      (node (ref "R47") (pin "2") (pinfunction "2_2") (pintype "passive"))
    )
    (net (code "46") (name "Net-(P1-Pad17)") (class "Default")
      (node (ref "P1") (pin "17") (pinfunction "17_17") (pintype "passive"))
      (node (ref "R51") (pin "1") (pinfunction "1_1") (pintype "passive"))
    )
    (net (code "47") (name "Net-(P1-Pad18)") (class "Default")
      (node (ref "P1") (pin "18") (pinfunction "18_18") (pintype "passive"))
      (node (ref "R50") (pin "2") (pinfunction "2_2") (pintype "passive"))
    )
    (net (code "48") (name "Net-(P1-Pad19)") (class "Default")
      (node (ref "P1") (pin "19") (pinfunction "19_19") (pintype "passive"))
      (node (ref "R54") (pin "1") (pinfunction "1_1") (pintype "passive"))
    )
    (net (code "49") (name "Net-(P1-Pad20)") (class "Default")
      (node (ref "P1") (pin "20") (pinfunction "20_20") (pintype "passive"))
      (node (ref "R53") (pin "2") (pinfunction "2_2") (pintype "passive"))
    )
    (net (code "50") (name "Net-(P2-Pad5)") (class "Default")
      (node (ref "P2") (pin "5") (pinfunction "5_5") (pintype "passive"))
      (node (ref "R36") (pin "1") (pinfunction "1_1") (pintype "passive"))
    )
    (net (code "51") (name "Net-(P2-Pad6)") (class "Default")
      (node (ref "P2") (pin "6") (pinfunction "6_6") (pintype "passive"))
      (node (ref "R35") (pin "2") (pinfunction "2_2") (pintype "passive"))
    )
    (net (code "52") (name "Net-(P2-Pad7)") (class "Default")
      (node (ref "P2") (pin "7") (pinfunction "7_7") (pintype "passive"))
      (node (ref "R39") (pin "1") (pinfunction "1_1") (pintype "passive"))
    )
    (net (code "53") (name "Net-(P2-Pad8)") (class "Default")
      (node (ref "P2") (pin "8") (pinfunction "8_8") (pintype "passive"))
      (node (ref "R38") (pin "2") (pinfunction "2_2") (pintype "passive"))
    )
    (net (code "54") (name "Net-(P2-Pad10)") (class "Default")
      (node (ref "P2") (pin "10") (pinfunction "10_10") (pintype "passive"))
      (node (ref "R42") (pin "2") (pinfunction "2_2") (pintype "passive"))
    )
    (net (code "55") (name "Net-(P2-Pad14)") (class "Default")
      (node (ref "P2") (pin "14") (pinfunction "14_14") (pintype "passive"))
      (node (ref "R46") (pin "2") (pinfunction "2_2") (pintype "passive"))
    )
    (net (code "56") (name "Net-(P2-Pad15)") (class "Default")
      (node (ref "P2") (pin "15") (pinfunction "15_15") (pintype "passive"))
      (node (ref "R49") (pin "1") (pinfunction "1_1") (pintype "passive"))
    )
    (net (code "57") (name "Net-(P2-Pad16)") (class "Default")
      (node (ref "P2") (pin "16") (pinfunction "16_16") (pintype "passive"))
      (node (ref "R48") (pin "2") (pinfunction "2_2") (pintype "passive"))
    )
    (net (code "58") (name "Net-(P2-Pad17)") (class "Default")
      (node (ref "P2") (pin "17") (pinfunction "17_17") (pintype "passive"))
      (node (ref "R52") (pin "1") (pinfunction "1_1") (pintype "passive"))
    )
    (net (code "59") (name "Net-(P2-Pad19)") (class "Default")
      (node (ref "P2") (pin "19") (pinfunction "19_19") (pintype "passive"))
      (node (ref "R55") (pin "1") (pinfunction "1_1") (pintype "passive"))
    )
    (net (code "60") (name "Net-(Q1A-G)") (class "Default")
      (node (ref "Q1") (pin "2") (pinfunction "G_2") (pintype "passive"))
      (node (ref "Q1") (pin "5") (pinfunction "G_5") (pintype "passive"))
      (node (ref "Q2") (pin "1") (pinfunction "G_1") (pintype "passive"))
      (node (ref "R63") (pin "1") (pinfunction "1_1") (pintype "passive"))
      (node (ref "SW3") (pin "3") (pinfunction "3_3") (pintype "passive"))
    )
    (net (code "61") (name "Net-(Q1A-S)") (class "Default")
      (node (ref "Q1") (pin "1") (pinfunction "S_1") (pintype "passive"))
      (node (ref "R61") (pin "1") (pinfunction "1_1") (pintype "passive"))
    )
    (net (code "62") (name "Net-(Q1B-S)") (class "Default")
      (node (ref "Q1") (pin "4") (pinfunction "S_4") (pintype "passive"))
      (node (ref "R62") (pin "1") (pinfunction "1_1") (pintype "passive"))
    )
    (net (code "63") (name "Net-(Q3-D)") (class "Default")
      (node (ref "Q3") (pin "3") (pinfunction "D_3") (pintype "passive"))
      (node (ref "R65") (pin "2") (pinfunction "2_2") (pintype "passive"))
    )
    (net (code "64") (name "Net-(Q3-G)") (class "Default")
      (node (ref "Q3") (pin "1") (pinfunction "G_1") (pintype "passive"))
      (node (ref "R67") (pin "2") (pinfunction "2_2") (pintype "passive"))
    )
    (net (code "65") (name "Net-(Q4-D)") (class "Default")
      (node (ref "Q4") (pin "3") (pinfunction "D_3") (pintype "passive"))
      (node (ref "R66") (pin "2") (pinfunction "2_2") (pintype "passive"))
    )
    (net (code "66") (name "Net-(Q4-G)") (class "Default")
      (node (ref "Q4") (pin "1") (pinfunction "G_1") (pintype "passive"))
      (node (ref "R68") (pin "2") (pinfunction "2_2") (pintype "passive"))
    )
    (net (code "67") (name "Net-(R69-Pad2)") (class "Default")
      (node (ref "R69") (pin "2") (pinfunction "2_2") (pintype "passive"))
      (node (ref "SW1") (pin "1") (pinfunction "1_1") (pintype "passive"))
    )
    (net (code "68") (name "Net-(R70-Pad2)") (class "Default")
      (node (ref "R70") (pin "2") (pinfunction "2_2") (pintype "passive"))
      (node (ref "SW2") (pin "1") (pinfunction "1_1") (pintype "passive"))
    )
    (net (code "69") (name "Net-(R72-Pad2)") (class "Default")
      (node (ref "R72") (pin "2") (pinfunction "2_2") (pintype "passive"))
      (node (ref "SW3") (pin "4") (pinfunction "4_4") (pintype "passive"))
    )
    (net (code "70") (name "Net-(U3-FB)") (class "Default")
      (node (ref "C31") (pin "2") (pinfunction "2_2") (pintype "passive"))
      (node (ref "R58") (pin "1") (pinfunction "1_1") (pintype "passive"))
      (node (ref "R59") (pin "2") (pinfunction "2_2") (pintype "passive"))
      (node (ref "U3") (pin "5") (pinfunction "FB_5") (pintype "input"))
    )
    (net (code "71") (name "SOP0") (class "Default")
      (node (ref "Q1") (pin "3") (pinfunction "D_3") (pintype "passive"))
    )
    (net (code "72") (name "SOP1") (class "Default")
      (node (ref "Q1") (pin "6") (pinfunction "D_6") (pintype "passive"))
      (node (ref "R48") (pin "1") (pinfunction "1_1") (pintype "passive"))
    )
    (net (code "73") (name "VBAT_CC") (class "Default")
      (node (ref "C33") (pin "1") (pinfunction "1_1") (pintype "passive"))
      (node (ref "C34") (pin "1") (pinfunction "1_1") (pintype "passive"))
      (node (ref "J8") (pin "2") (pinfunction "2_2") (pintype "passive"))
      (node (ref "R57") (pin "2") (pinfunction "2_2") (pintype "passive"))
    )
    (net (code "74") (name "VCC_BRD") (class "Default")
      (node (ref "D5") (pin "2") (pinfunction "A_2") (pintype "passive"))
      (node (ref "D6") (pin "2") (pinfunction "A_2") (pintype "passive"))
      (node (ref "J7") (pin "2") (pinfunction "2_2") (pintype "passive"))
      (node (ref "J8") (pin "1") (pinfunction "1_1") (pintype "passive"))
      (node (ref "Q2") (pin "2") (pinfunction "S_2") (pintype "passive"))
      (node (ref "R32") (pin "2") (pinfunction "2_2") (pintype "passive"))
      (node (ref "R56") (pin "1") (pinfunction "1_1") (pintype "passive"))
      (node (ref "R57") (pin "1") (pinfunction "1_1") (pintype "passive"))
      (node (ref "R61") (pin "2") (pinfunction "2_2") (pintype "passive"))
      (node (ref "R62") (pin "2") (pinfunction "2_2") (pintype "passive"))
      (node (ref "R63") (pin "2") (pinfunction "2_2") (pintype "passive"))
    )
    (net (code "75") (name "VCC_BRD_5V") (class "Default")
      (node (ref "C35") (pin "1") (pinfunction "1_1") (pintype "passive"))
      (node (ref "D1") (pin "1") (pinfunction "K_1") (pintype "passive"))
      (node (ref "D2") (pin "1") (pinfunction "K_1") (pintype "passive"))
      (node (ref "U3") (pin "1") (pinfunction "EN_1") (pintype "input"))
      (node (ref "U3") (pin "2") (pinfunction "IN_2") (pintype "power_in"))
    )
    (net (code "76") (name "VCC_LDO_3V3") (class "Default")
      (node (ref "C31") (pin "1") (pinfunction "1_1") (pintype "passive"))
      (node (ref "C32") (pin "1") (pinfunction "1_1") (pintype "passive"))
      (node (ref "J7") (pin "3") (pinfunction "3_3") (pintype "passive"))
      (node (ref "R58") (pin "2") (pinfunction "2_2") (pintype "passive"))
      (node (ref "U3") (pin "4") (pinfunction "OUT_4") (pintype "power_in"))
    )
    (net (code "77") (name "VCC_MCU_3V3") (class "Default")
      (node (ref "J7") (pin "1") (pinfunction "1_1") (pintype "passive"))
      (node (ref "P2") (pin "2") (pinfunction "2_2") (pintype "passive"))
    )
    (net (code "78") (name "VCC_MCU_5V") (class "Default")
      (node (ref "D1") (pin "2") (pinfunction "A_2") (pintype "passive"))
      (node (ref "P2") (pin "1") (pinfunction "1_1") (pintype "passive"))
    )
    (net (code "79") (name "unconnected-(J6-Pad2)") (class "Default")
      (node (ref "J6") (pin "2") (pintype "passive+no_connect"))
    )
    (net (code "80") (name "unconnected-(J6-Pad3)") (class "Default")
      (node (ref "J6") (pin "3") (pintype "passive+no_connect"))
    )
    (net (code "81") (name "unconnected-(J6-Pad4)") (class "Default")
      (node (ref "J6") (pin "4") (pintype "passive+no_connect"))
    )
    (net (code "82") (name "unconnected-(P1-Pad6)") (class "Default")
      (node (ref "P1") (pin "6") (pinfunction "6_6") (pintype "passive+no_connect"))
    )
    (net (code "83") (name "unconnected-(P1-Pad7)") (class "Default")
      (node (ref "P1") (pin "7") (pinfunction "7_7") (pintype "passive+no_connect"))
    )
    (net (code "84") (name "unconnected-(P1-Pad12)") (class "Default")
      (node (ref "P1") (pin "12") (pinfunction "12_12") (pintype "passive+no_connect"))
    )
    (net (code "85") (name "unconnected-(P1-Pad15)") (class "Default")
      (node (ref "P1") (pin "15") (pinfunction "15_15") (pintype "passive+no_connect"))
    )
    (net (code "86") (name "unconnected-(P2-Pad4)") (class "Default")
      (node (ref "P2") (pin "4") (pinfunction "4_4") (pintype "passive+no_connect"))
    )
    (net (code "87") (name "unconnected-(P2-Pad9)") (class "Default")
      (node (ref "P2") (pin "9") (pinfunction "9_9") (pintype "passive+no_connect"))
    )
    (net (code "88") (name "unconnected-(P2-Pad11)") (class "Default")
      (node (ref "P2") (pin "11") (pinfunction "11_11") (pintype "passive+no_connect"))
    )
    (net (code "89") (name "unconnected-(P2-Pad12)") (class "Default")
      (node (ref "P2") (pin "12") (pinfunction "12_12") (pintype "passive+no_connect"))
    )
    (net (code "90") (name "unconnected-(P2-Pad13)") (class "Default")
      (node (ref "P2") (pin "13") (pinfunction "13_13") (pintype "passive+no_connect"))
    )
    (net (code "91") (name "unconnected-(P2-Pad18)") (class "Default")
      (node (ref "P2") (pin "18") (pinfunction "18_18") (pintype "passive+no_connect"))
    )
    (net (code "92") (name "unconnected-(P2-Pad20)") (class "Default")
      (node (ref "P2") (pin "20") (pinfunction "20_20") (pintype "passive+no_connect"))
    )
  )
)
